# Rev_A.net
KiCad netlist of a schematic drawn in EAGLE
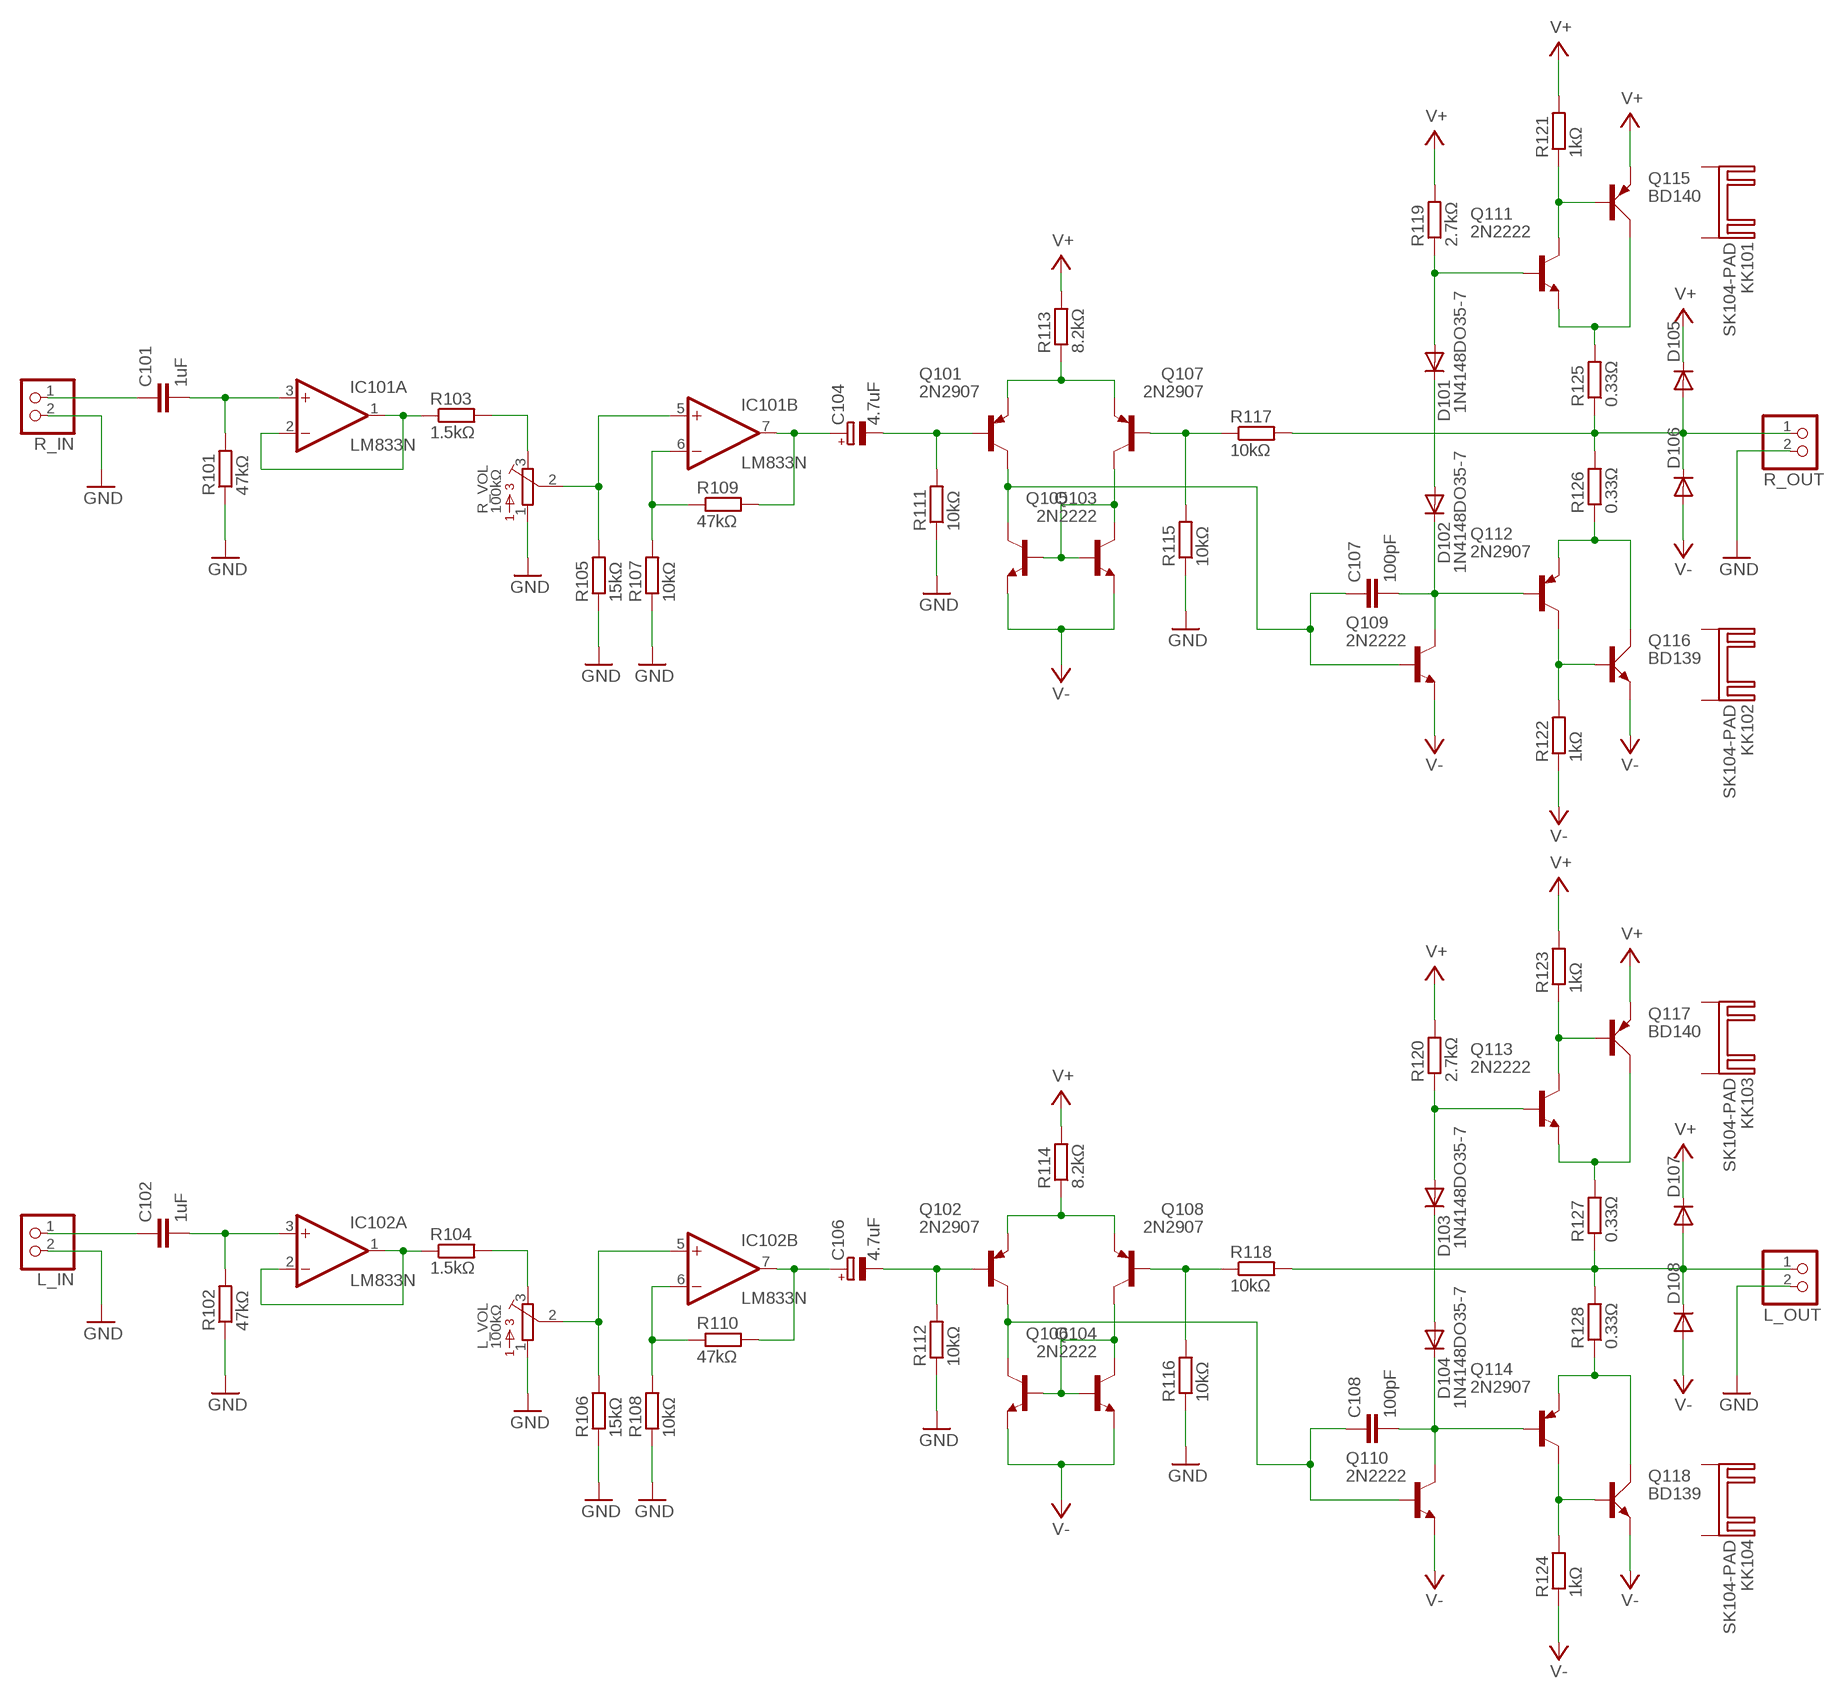
[diagram p0: schematic, sheet 1]
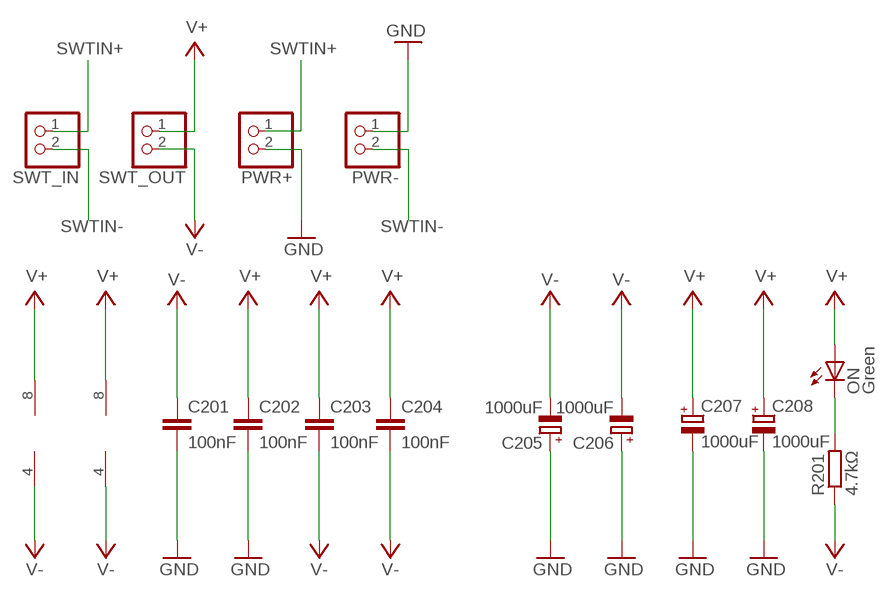
[diagram p1: schematic, sheet 2]

(export (version "E")
  (design (tool "Eeschema 10.0.6"))
  (components
    (comp (ref "C201")
      (value "100nF")
      (footprint "eagle-import:C025-025X050")
      (libsource (lib "eagle-import") (part "C-EU025-025X050"))
    )
    (comp (ref "C202")
      (value "100nF")
      (footprint "eagle-import:C025-025X050")
      (libsource (lib "eagle-import") (part "C-EU025-025X050"))
    )
    (comp (ref "C203")
      (value "100nF")
      (footprint "eagle-import:C025-025X050")
      (libsource (lib "eagle-import") (part "C-EU025-025X050"))
    )
    (comp (ref "C204")
      (value "100nF")
      (footprint "eagle-import:C025-025X050")
      (libsource (lib "eagle-import") (part "C-EU025-025X050"))
    )
    (comp (ref "C205")
      (value "1000uF")
      (footprint "eagle-import:E5-10,5")
      (libsource (lib "eagle-import") (part "CPOL-EUE5-10.5"))
    )
    (comp (ref "C206")
      (value "1000uF")
      (footprint "eagle-import:E5-10,5")
      (libsource (lib "eagle-import") (part "CPOL-EUE5-10.5"))
    )
    (comp (ref "C207")
      (value "1000uF")
      (footprint "eagle-import:E5-10,5")
      (libsource (lib "eagle-import") (part "CPOL-EUE5-10.5"))
    )
    (comp (ref "C208")
      (value "1000uF")
      (footprint "eagle-import:E5-10,5")
      (libsource (lib "eagle-import") (part "CPOL-EUE5-10.5"))
    )
    (comp (ref "IC101")
      (value "LM833N")
      (footprint "eagle-import:DIL08")
      (libsource (lib "eagle-import") (part "LM833N"))
    )
    (comp (ref "IC102")
      (value "LM833N")
      (footprint "eagle-import:DIL08")
      (libsource (lib "eagle-import") (part "LM833N"))
    )
    (comp (ref "ON")
      (value "Green")
      (footprint "eagle-import:LED5MM")
      (libsource (lib "eagle-import") (part "LED5MM"))
    )
    (comp (ref "PWR+")
      (value "JST_2PIN-THM")
      (footprint "eagle-import:JST-PH-2-THM")
      (libsource (lib "eagle-import") (part "JST_2PIN-THM"))
    )
    (comp (ref "PWR-")
      (value "JST_2PIN-THM")
      (footprint "eagle-import:JST-PH-2-THM")
      (libsource (lib "eagle-import") (part "JST_2PIN-THM"))
    )
    (comp (ref "R201")
      (value "4.7kΩ")
      (footprint "eagle-import:0207_10")
      (libsource (lib "eagle-import") (part "R-EU_0207/10"))
    )
    (comp (ref "SWT_IN")
      (value "JST_2PIN-THM")
      (footprint "eagle-import:JST-PH-2-THM")
      (libsource (lib "eagle-import") (part "JST_2PIN-THM"))
    )
    (comp (ref "SWT_OUT")
      (value "JST_2PIN-THM")
      (footprint "eagle-import:JST-PH-2-THM")
      (libsource (lib "eagle-import") (part "JST_2PIN-THM"))
    )
    (comp (ref "C101")
      (value "1uF")
      (footprint "eagle-import:C050-050X075")
      (libsource (lib "eagle-import") (part "C-EU050-050X075"))
    )
    (comp (ref "C102")
      (value "1uF")
      (footprint "eagle-import:C050-050X075")
      (libsource (lib "eagle-import") (part "C-EU050-050X075"))
    )
    (comp (ref "C104")
      (value "4.7uF")
      (footprint "eagle-import:E2-5")
      (libsource (lib "eagle-import") (part "CPOL-EUE2-5"))
    )
    (comp (ref "C106")
      (value "4.7uF")
      (footprint "eagle-import:E2-5")
      (libsource (lib "eagle-import") (part "CPOL-EUE2-5"))
    )
    (comp (ref "C107")
      (value "100pF")
      (footprint "eagle-import:C050-050X075")
      (libsource (lib "eagle-import") (part "C-EU050-050X075"))
    )
    (comp (ref "C108")
      (value "100pF")
      (footprint "eagle-import:C050-050X075")
      (libsource (lib "eagle-import") (part "C-EU050-050X075"))
    )
    (comp (ref "D101")
      (value "1N4148DO35-7")
      (footprint "eagle-import:DO35-7")
      (libsource (lib "eagle-import") (part "1N4148DO35-7"))
    )
    (comp (ref "D102")
      (value "1N4148DO35-7")
      (footprint "eagle-import:DO35-7")
      (libsource (lib "eagle-import") (part "1N4148DO35-7"))
    )
    (comp (ref "D103")
      (value "1N4148DO35-7")
      (footprint "eagle-import:DO35-7")
      (libsource (lib "eagle-import") (part "1N4148DO35-7"))
    )
    (comp (ref "D104")
      (value "1N4148DO35-7")
      (footprint "eagle-import:DO35-7")
      (libsource (lib "eagle-import") (part "1N4148DO35-7"))
    )
    (comp (ref "D105")
      (value "1N4148DO35-7")
      (footprint "eagle-import:DO35-7")
      (libsource (lib "eagle-import") (part "1N4148DO35-7"))
    )
    (comp (ref "D106")
      (value "1N4148DO35-7")
      (footprint "eagle-import:DO35-7")
      (libsource (lib "eagle-import") (part "1N4148DO35-7"))
    )
    (comp (ref "D107")
      (value "1N4148DO35-7")
      (footprint "eagle-import:DO35-7")
      (libsource (lib "eagle-import") (part "1N4148DO35-7"))
    )
    (comp (ref "D108")
      (value "1N4148DO35-7")
      (footprint "eagle-import:DO35-7")
      (libsource (lib "eagle-import") (part "1N4148DO35-7"))
    )
    (comp (ref "KK101")
      (value "SK104-PAD")
      (footprint "eagle-import:SK104-PAD")
      (libsource (lib "eagle-import") (part "SK104-PAD"))
    )
    (comp (ref "KK102")
      (value "SK104-PAD")
      (footprint "eagle-import:SK104-PAD")
      (libsource (lib "eagle-import") (part "SK104-PAD"))
    )
    (comp (ref "KK103")
      (value "SK104-PAD")
      (footprint "eagle-import:SK104-PAD")
      (libsource (lib "eagle-import") (part "SK104-PAD"))
    )
    (comp (ref "KK104")
      (value "SK104-PAD")
      (footprint "eagle-import:SK104-PAD")
      (libsource (lib "eagle-import") (part "SK104-PAD"))
    )
    (comp (ref "L_IN")
      (value "JST_2PIN-THM")
      (footprint "eagle-import:JST-PH-2-THM")
      (libsource (lib "eagle-import") (part "JST_2PIN-THM"))
    )
    (comp (ref "L_OUT")
      (value "JST_2PIN-THM")
      (footprint "eagle-import:JST-PH-2-THM")
      (libsource (lib "eagle-import") (part "JST_2PIN-THM"))
    )
    (comp (ref "L_VOL")
      (value "100kΩ")
      (footprint "eagle-import:3362U")
      (libsource (lib "eagle-import") (part "3362U"))
    )
    (comp (ref "Q101")
      (value "2N2907")
      (footprint "eagle-import:TO18")
      (libsource (lib "eagle-import") (part "2N2907"))
    )
    (comp (ref "Q102")
      (value "2N2907")
      (footprint "eagle-import:TO18")
      (libsource (lib "eagle-import") (part "2N2907"))
    )
    (comp (ref "Q103")
      (value "2N2222")
      (footprint "eagle-import:TO18")
      (libsource (lib "eagle-import") (part "2N2222"))
    )
    (comp (ref "Q104")
      (value "2N2222")
      (footprint "eagle-import:TO18")
      (libsource (lib "eagle-import") (part "2N2222"))
    )
    (comp (ref "Q105")
      (value "2N2222")
      (footprint "eagle-import:TO18")
      (libsource (lib "eagle-import") (part "2N2222"))
    )
    (comp (ref "Q106")
      (value "2N2222")
      (footprint "eagle-import:TO18")
      (libsource (lib "eagle-import") (part "2N2222"))
    )
    (comp (ref "Q107")
      (value "2N2907")
      (footprint "eagle-import:TO18")
      (libsource (lib "eagle-import") (part "2N2907"))
    )
    (comp (ref "Q108")
      (value "2N2907")
      (footprint "eagle-import:TO18")
      (libsource (lib "eagle-import") (part "2N2907"))
    )
    (comp (ref "Q109")
      (value "2N2222")
      (footprint "eagle-import:TO18")
      (libsource (lib "eagle-import") (part "2N2222"))
    )
    (comp (ref "Q110")
      (value "2N2222")
      (footprint "eagle-import:TO18")
      (libsource (lib "eagle-import") (part "2N2222"))
    )
    (comp (ref "Q111")
      (value "2N2222")
      (footprint "eagle-import:TO18")
      (libsource (lib "eagle-import") (part "2N2222"))
    )
    (comp (ref "Q112")
      (value "2N2907")
      (footprint "eagle-import:TO18")
      (libsource (lib "eagle-import") (part "2N2907"))
    )
    (comp (ref "Q113")
      (value "2N2222")
      (footprint "eagle-import:TO18")
      (libsource (lib "eagle-import") (part "2N2222"))
    )
    (comp (ref "Q114")
      (value "2N2907")
      (footprint "eagle-import:TO18")
      (libsource (lib "eagle-import") (part "2N2907"))
    )
    (comp (ref "Q115")
      (value "BD140")
      (footprint "eagle-import:TO126AV")
      (libsource (lib "eagle-import") (part "BD140"))
    )
    (comp (ref "Q116")
      (value "BD139")
      (footprint "eagle-import:TO126AV")
      (libsource (lib "eagle-import") (part "BD139"))
    )
    (comp (ref "Q117")
      (value "BD140")
      (footprint "eagle-import:TO126AV")
      (libsource (lib "eagle-import") (part "BD140"))
    )
    (comp (ref "Q118")
      (value "BD139")
      (footprint "eagle-import:TO126AV")
      (libsource (lib "eagle-import") (part "BD139"))
    )
    (comp (ref "R101")
      (value "47kΩ")
      (footprint "eagle-import:0207_10")
      (libsource (lib "eagle-import") (part "R-EU_0207/10"))
    )
    (comp (ref "R102")
      (value "47kΩ")
      (footprint "eagle-import:0207_10")
      (libsource (lib "eagle-import") (part "R-EU_0207/10"))
    )
    (comp (ref "R103")
      (value "1.5kΩ")
      (footprint "eagle-import:0207_10")
      (libsource (lib "eagle-import") (part "R-EU_0207/10"))
    )
    (comp (ref "R104")
      (value "1.5kΩ")
      (footprint "eagle-import:0207_10")
      (libsource (lib "eagle-import") (part "R-EU_0207/10"))
    )
    (comp (ref "R105")
      (value "15kΩ")
      (footprint "eagle-import:0207_10")
      (libsource (lib "eagle-import") (part "R-EU_0207/10"))
    )
    (comp (ref "R106")
      (value "15kΩ")
      (footprint "eagle-import:0207_10")
      (libsource (lib "eagle-import") (part "R-EU_0207/10"))
    )
    (comp (ref "R107")
      (value "10kΩ")
      (footprint "eagle-import:0207_10")
      (libsource (lib "eagle-import") (part "R-EU_0207/10"))
    )
    (comp (ref "R108")
      (value "10kΩ")
      (footprint "eagle-import:0207_10")
      (libsource (lib "eagle-import") (part "R-EU_0207/10"))
    )
    (comp (ref "R109")
      (value "47kΩ")
      (footprint "eagle-import:0207_10")
      (libsource (lib "eagle-import") (part "R-EU_0207/10"))
    )
    (comp (ref "R110")
      (value "47kΩ")
      (footprint "eagle-import:0207_10")
      (libsource (lib "eagle-import") (part "R-EU_0207/10"))
    )
    (comp (ref "R111")
      (value "10kΩ")
      (footprint "eagle-import:0207_10")
      (libsource (lib "eagle-import") (part "R-EU_0207/10"))
    )
    (comp (ref "R112")
      (value "10kΩ")
      (footprint "eagle-import:0207_10")
      (libsource (lib "eagle-import") (part "R-EU_0207/10"))
    )
    (comp (ref "R113")
      (value "8.2kΩ")
      (footprint "eagle-import:0207_10")
      (libsource (lib "eagle-import") (part "R-EU_0207/10"))
    )
    (comp (ref "R114")
      (value "8.2kΩ")
      (footprint "eagle-import:0207_10")
      (libsource (lib "eagle-import") (part "R-EU_0207/10"))
    )
    (comp (ref "R115")
      (value "10kΩ")
      (footprint "eagle-import:0207_10")
      (libsource (lib "eagle-import") (part "R-EU_0207/10"))
    )
    (comp (ref "R116")
      (value "10kΩ")
      (footprint "eagle-import:0207_10")
      (libsource (lib "eagle-import") (part "R-EU_0207/10"))
    )
    (comp (ref "R117")
      (value "10kΩ")
      (footprint "eagle-import:0207_10")
      (libsource (lib "eagle-import") (part "R-EU_0207/10"))
    )
    (comp (ref "R118")
      (value "10kΩ")
      (footprint "eagle-import:0207_10")
      (libsource (lib "eagle-import") (part "R-EU_0207/10"))
    )
    (comp (ref "R119")
      (value "2.7kΩ")
      (footprint "eagle-import:0207_10")
      (libsource (lib "eagle-import") (part "R-EU_0207/10"))
    )
    (comp (ref "R120")
      (value "2.7kΩ")
      (footprint "eagle-import:0207_10")
      (libsource (lib "eagle-import") (part "R-EU_0207/10"))
    )
    (comp (ref "R121")
      (value "1kΩ")
      (footprint "eagle-import:0207_10")
      (libsource (lib "eagle-import") (part "R-EU_0207/10"))
    )
    (comp (ref "R122")
      (value "1kΩ")
      (footprint "eagle-import:0207_10")
      (libsource (lib "eagle-import") (part "R-EU_0207/10"))
    )
    (comp (ref "R123")
      (value "1kΩ")
      (footprint "eagle-import:0207_10")
      (libsource (lib "eagle-import") (part "R-EU_0207/10"))
    )
    (comp (ref "R124")
      (value "1kΩ")
      (footprint "eagle-import:0207_10")
      (libsource (lib "eagle-import") (part "R-EU_0207/10"))
    )
    (comp (ref "R125")
      (value "0.33Ω")
      (footprint "eagle-import:0309_12")
      (libsource (lib "eagle-import") (part "R-EU_0309/12"))
    )
    (comp (ref "R126")
      (value "0.33Ω")
      (footprint "eagle-import:0309_12")
      (libsource (lib "eagle-import") (part "R-EU_0309/12"))
    )
    (comp (ref "R127")
      (value "0.33Ω")
      (footprint "eagle-import:0309_12")
      (libsource (lib "eagle-import") (part "R-EU_0309/12"))
    )
    (comp (ref "R128")
      (value "0.33Ω")
      (footprint "eagle-import:0309_12")
      (libsource (lib "eagle-import") (part "R-EU_0309/12"))
    )
    (comp (ref "R_IN")
      (value "JST_2PIN-THM")
      (footprint "eagle-import:JST-PH-2-THM")
      (libsource (lib "eagle-import") (part "JST_2PIN-THM"))
    )
    (comp (ref "R_OUT")
      (value "JST_2PIN-THM")
      (footprint "eagle-import:JST-PH-2-THM")
      (libsource (lib "eagle-import") (part "JST_2PIN-THM"))
    )
    (comp (ref "R_VOL")
      (value "100kΩ")
      (footprint "eagle-import:3362U")
      (libsource (lib "eagle-import") (part "3362U"))
    )
  )
  (nets
    (net (code "1") (name "GND") (class "Default")
      (node (ref "C201") (pin "2") (pinfunction "2_2") (pintype "passive"))
      (node (ref "C202") (pin "2") (pinfunction "2_2") (pintype "passive"))
      (node (ref "C205") (pin "+") (pinfunction "+_+") (pintype "passive"))
      (node (ref "C206") (pin "+") (pinfunction "+_+") (pintype "passive"))
      (node (ref "C207") (pin "-") (pinfunction "-_-") (pintype "passive"))
      (node (ref "C208") (pin "-") (pinfunction "-_-") (pintype "passive"))
      (node (ref "L_IN") (pin "2") (pinfunction "1_2") (pintype "passive"))
      (node (ref "L_OUT") (pin "2") (pinfunction "1_2") (pintype "passive"))
      (node (ref "L_VOL") (pin "1") (pinfunction "1_1") (pintype "passive"))
      (node (ref "PWR+") (pin "2") (pinfunction "1_2") (pintype "passive"))
      (node (ref "PWR-") (pin "1") (pinfunction "2_1") (pintype "passive"))
      (node (ref "R101") (pin "1") (pinfunction "1_1") (pintype "passive"))
      (node (ref "R102") (pin "1") (pinfunction "1_1") (pintype "passive"))
      (node (ref "R105") (pin "1") (pinfunction "1_1") (pintype "passive"))
      (node (ref "R106") (pin "1") (pinfunction "1_1") (pintype "passive"))
      (node (ref "R107") (pin "1") (pinfunction "1_1") (pintype "passive"))
      (node (ref "R108") (pin "1") (pinfunction "1_1") (pintype "passive"))
      (node (ref "R111") (pin "1") (pinfunction "1_1") (pintype "passive"))
      (node (ref "R112") (pin "1") (pinfunction "1_1") (pintype "passive"))
      (node (ref "R115") (pin "1") (pinfunction "1_1") (pintype "passive"))
      (node (ref "R116") (pin "1") (pinfunction "1_1") (pintype "passive"))
      (node (ref "R_IN") (pin "2") (pinfunction "1_2") (pintype "passive"))
      (node (ref "R_OUT") (pin "2") (pinfunction "1_2") (pintype "passive"))
      (node (ref "R_VOL") (pin "1") (pinfunction "1_1") (pintype "passive"))
    )
    (net (code "2") (name "Net-(D101-PadC)") (class "Default")
      (node (ref "D101") (pin "C") (pinfunction "C_C") (pintype "passive"))
      (node (ref "D102") (pin "A") (pinfunction "A_A") (pintype "passive"))
    )
    (net (code "3") (name "Net-(D103-PadC)") (class "Default")
      (node (ref "D103") (pin "C") (pinfunction "C_C") (pintype "passive"))
      (node (ref "D104") (pin "A") (pinfunction "A_A") (pintype "passive"))
    )
    (net (code "4") (name "Net-(IC101A-+IN)") (class "Default")
      (node (ref "C101") (pin "2") (pinfunction "2_2") (pintype "passive"))
      (node (ref "IC101") (pin "3") (pinfunction "+IN_3") (pintype "input"))
      (node (ref "R101") (pin "2") (pinfunction "2_2") (pintype "passive"))
    )
    (net (code "5") (name "Net-(IC101A--IN)") (class "Default")
      (node (ref "IC101") (pin "1") (pinfunction "OUT_1") (pintype "output"))
      (node (ref "IC101") (pin "2") (pinfunction "-IN_2") (pintype "input"))
      (node (ref "R103") (pin "1") (pinfunction "1_1") (pintype "passive"))
    )
    (net (code "6") (name "Net-(IC101B-+IN)") (class "Default")
      (node (ref "IC101") (pin "5") (pinfunction "+IN_5") (pintype "input"))
      (node (ref "R105") (pin "2") (pinfunction "2_2") (pintype "passive"))
      (node (ref "R_VOL") (pin "2") (pinfunction "2_2") (pintype "passive"))
    )
    (net (code "7") (name "Net-(IC101B--IN)") (class "Default")
      (node (ref "IC101") (pin "6") (pinfunction "-IN_6") (pintype "input"))
      (node (ref "R107") (pin "2") (pinfunction "2_2") (pintype "passive"))
      (node (ref "R109") (pin "1") (pinfunction "1_1") (pintype "passive"))
    )
    (net (code "8") (name "Net-(IC101B-OUT)") (class "Default")
      (node (ref "C104") (pin "+") (pinfunction "+_+") (pintype "passive"))
      (node (ref "IC101") (pin "7") (pinfunction "OUT_7") (pintype "output"))
      (node (ref "R109") (pin "2") (pinfunction "2_2") (pintype "passive"))
    )
    (net (code "9") (name "Net-(IC102A-+IN)") (class "Default")
      (node (ref "C102") (pin "2") (pinfunction "2_2") (pintype "passive"))
      (node (ref "IC102") (pin "3") (pinfunction "+IN_3") (pintype "input"))
      (node (ref "R102") (pin "2") (pinfunction "2_2") (pintype "passive"))
    )
    (net (code "10") (name "Net-(IC102A--IN)") (class "Default")
      (node (ref "IC102") (pin "1") (pinfunction "OUT_1") (pintype "output"))
      (node (ref "IC102") (pin "2") (pinfunction "-IN_2") (pintype "input"))
      (node (ref "R104") (pin "1") (pinfunction "1_1") (pintype "passive"))
    )
    (net (code "11") (name "Net-(IC102B-+IN)") (class "Default")
      (node (ref "IC102") (pin "5") (pinfunction "+IN_5") (pintype "input"))
      (node (ref "L_VOL") (pin "2") (pinfunction "2_2") (pintype "passive"))
      (node (ref "R106") (pin "2") (pinfunction "2_2") (pintype "passive"))
    )
    (net (code "12") (name "Net-(IC102B--IN)") (class "Default")
      (node (ref "IC102") (pin "6") (pinfunction "-IN_6") (pintype "input"))
      (node (ref "R108") (pin "2") (pinfunction "2_2") (pintype "passive"))
      (node (ref "R110") (pin "1") (pinfunction "1_1") (pintype "passive"))
    )
    (net (code "13") (name "Net-(IC102B-OUT)") (class "Default")
      (node (ref "C106") (pin "+") (pinfunction "+_+") (pintype "passive"))
      (node (ref "IC102") (pin "7") (pinfunction "OUT_7") (pintype "output"))
      (node (ref "R110") (pin "2") (pinfunction "2_2") (pintype "passive"))
    )
    (net (code "14") (name "Net-(L_IN-2)") (class "Default")
      (node (ref "C102") (pin "1") (pinfunction "1_1") (pintype "passive"))
      (node (ref "L_IN") (pin "1") (pinfunction "2_1") (pintype "passive"))
    )
    (net (code "15") (name "Net-(L_OUT-2)") (class "Default")
      (node (ref "D107") (pin "A") (pinfunction "A_A") (pintype "passive"))
      (node (ref "D108") (pin "C") (pinfunction "C_C") (pintype "passive"))
      (node (ref "L_OUT") (pin "1") (pinfunction "2_1") (pintype "passive"))
      (node (ref "R118") (pin "2") (pinfunction "2_2") (pintype "passive"))
      (node (ref "R127") (pin "1") (pinfunction "1_1") (pintype "passive"))
      (node (ref "R128") (pin "2") (pinfunction "2_2") (pintype "passive"))
    )
    (net (code "16") (name "Net-(L_VOL-Pad3)") (class "Default")
      (node (ref "L_VOL") (pin "3") (pinfunction "3_3") (pintype "passive"))
      (node (ref "R104") (pin "2") (pinfunction "2_2") (pintype "passive"))
    )
    (net (code "17") (name "Net-(ON-C)") (class "Default")
      (node (ref "ON") (pin "K") (pinfunction "C_K") (pintype "passive"))
      (node (ref "R201") (pin "2") (pinfunction "2_2") (pintype "passive"))
    )
    (net (code "18") (name "Net-(Q101-B)") (class "Default")
      (node (ref "C104") (pin "-") (pinfunction "-_-") (pintype "passive"))
      (node (ref "Q101") (pin "2") (pinfunction "B_2") (pintype "passive"))
      (node (ref "R111") (pin "2") (pinfunction "2_2") (pintype "passive"))
    )
    (net (code "19") (name "Net-(Q101-C)") (class "Default")
      (node (ref "C107") (pin "1") (pinfunction "1_1") (pintype "passive"))
      (node (ref "Q101") (pin "3") (pinfunction "C_3") (pintype "passive"))
      (node (ref "Q103") (pin "3") (pinfunction "C_3") (pintype "passive"))
      (node (ref "Q109") (pin "2") (pinfunction "B_2") (pintype "passive"))
    )
    (net (code "20") (name "Net-(Q101-E)") (class "Default")
      (node (ref "Q101") (pin "1") (pinfunction "E_1") (pintype "passive"))
      (node (ref "Q107") (pin "1") (pinfunction "E_1") (pintype "passive"))
      (node (ref "R113") (pin "1") (pinfunction "1_1") (pintype "passive"))
    )
    (net (code "21") (name "Net-(Q102-B)") (class "Default")
      (node (ref "C106") (pin "-") (pinfunction "-_-") (pintype "passive"))
      (node (ref "Q102") (pin "2") (pinfunction "B_2") (pintype "passive"))
      (node (ref "R112") (pin "2") (pinfunction "2_2") (pintype "passive"))
    )
    (net (code "22") (name "Net-(Q102-C)") (class "Default")
      (node (ref "C108") (pin "1") (pinfunction "1_1") (pintype "passive"))
      (node (ref "Q102") (pin "3") (pinfunction "C_3") (pintype "passive"))
      (node (ref "Q104") (pin "3") (pinfunction "C_3") (pintype "passive"))
      (node (ref "Q110") (pin "2") (pinfunction "B_2") (pintype "passive"))
    )
    (net (code "23") (name "Net-(Q102-E)") (class "Default")
      (node (ref "Q102") (pin "1") (pinfunction "E_1") (pintype "passive"))
      (node (ref "Q108") (pin "1") (pinfunction "E_1") (pintype "passive"))
      (node (ref "R114") (pin "1") (pinfunction "1_1") (pintype "passive"))
    )
    (net (code "24") (name "Net-(Q103-B)") (class "Default")
      (node (ref "Q103") (pin "2") (pinfunction "B_2") (pintype "passive"))
      (node (ref "Q105") (pin "2") (pinfunction "B_2") (pintype "passive"))
      (node (ref "Q105") (pin "3") (pinfunction "C_3") (pintype "passive"))
      (node (ref "Q107") (pin "3") (pinfunction "C_3") (pintype "passive"))
    )
    (net (code "25") (name "Net-(Q104-B)") (class "Default")
      (node (ref "Q104") (pin "2") (pinfunction "B_2") (pintype "passive"))
      (node (ref "Q106") (pin "2") (pinfunction "B_2") (pintype "passive"))
      (node (ref "Q106") (pin "3") (pinfunction "C_3") (pintype "passive"))
      (node (ref "Q108") (pin "3") (pinfunction "C_3") (pintype "passive"))
    )
    (net (code "26") (name "Net-(Q107-B)") (class "Default")
      (node (ref "Q107") (pin "2") (pinfunction "B_2") (pintype "passive"))
      (node (ref "R115") (pin "2") (pinfunction "2_2") (pintype "passive"))
      (node (ref "R117") (pin "1") (pinfunction "1_1") (pintype "passive"))
    )
    (net (code "27") (name "Net-(Q108-B)") (class "Default")
      (node (ref "Q108") (pin "2") (pinfunction "B_2") (pintype "passive"))
      (node (ref "R116") (pin "2") (pinfunction "2_2") (pintype "passive"))
      (node (ref "R118") (pin "1") (pinfunction "1_1") (pintype "passive"))
    )
    (net (code "28") (name "Net-(Q109-C)") (class "Default")
      (node (ref "C107") (pin "2") (pinfunction "2_2") (pintype "passive"))
      (node (ref "D102") (pin "C") (pinfunction "C_C") (pintype "passive"))
      (node (ref "Q109") (pin "3") (pinfunction "C_3") (pintype "passive"))
      (node (ref "Q112") (pin "2") (pinfunction "B_2") (pintype "passive"))
    )
    (net (code "29") (name "Net-(Q110-C)") (class "Default")
      (node (ref "C108") (pin "2") (pinfunction "2_2") (pintype "passive"))
      (node (ref "D104") (pin "C") (pinfunction "C_C") (pintype "passive"))
      (node (ref "Q110") (pin "3") (pinfunction "C_3") (pintype "passive"))
      (node (ref "Q114") (pin "2") (pinfunction "B_2") (pintype "passive"))
    )
    (net (code "30") (name "Net-(Q111-B)") (class "Default")
      (node (ref "D101") (pin "A") (pinfunction "A_A") (pintype "passive"))
      (node (ref "Q111") (pin "2") (pinfunction "B_2") (pintype "passive"))
      (node (ref "R119") (pin "1") (pinfunction "1_1") (pintype "passive"))
    )
    (net (code "31") (name "Net-(Q111-C)") (class "Default")
      (node (ref "Q111") (pin "3") (pinfunction "C_3") (pintype "passive"))
      (node (ref "Q115") (pin "B") (pinfunction "B_B") (pintype "passive"))
      (node (ref "R121") (pin "1") (pinfunction "1_1") (pintype "passive"))
    )
    (net (code "32") (name "Net-(Q111-E)") (class "Default")
      (node (ref "Q111") (pin "1") (pinfunction "E_1") (pintype "passive"))
      (node (ref "Q115") (pin "C") (pinfunction "C_C") (pintype "passive"))
      (node (ref "R125") (pin "2") (pinfunction "2_2") (pintype "passive"))
    )
    (net (code "33") (name "Net-(Q112-C)") (class "Default")
      (node (ref "Q112") (pin "3") (pinfunction "C_3") (pintype "passive"))
      (node (ref "Q116") (pin "B") (pinfunction "B_B") (pintype "passive"))
      (node (ref "R122") (pin "2") (pinfunction "2_2") (pintype "passive"))
    )
    (net (code "34") (name "Net-(Q112-E)") (class "Default")
      (node (ref "Q112") (pin "1") (pinfunction "E_1") (pintype "passive"))
      (node (ref "Q116") (pin "C") (pinfunction "C_C") (pintype "passive"))
      (node (ref "R126") (pin "1") (pinfunction "1_1") (pintype "passive"))
    )
    (net (code "35") (name "Net-(Q113-B)") (class "Default")
      (node (ref "D103") (pin "A") (pinfunction "A_A") (pintype "passive"))
      (node (ref "Q113") (pin "2") (pinfunction "B_2") (pintype "passive"))
      (node (ref "R120") (pin "1") (pinfunction "1_1") (pintype "passive"))
    )
    (net (code "36") (name "Net-(Q113-C)") (class "Default")
      (node (ref "Q113") (pin "3") (pinfunction "C_3") (pintype "passive"))
      (node (ref "Q117") (pin "B") (pinfunction "B_B") (pintype "passive"))
      (node (ref "R123") (pin "1") (pinfunction "1_1") (pintype "passive"))
    )
    (net (code "37") (name "Net-(Q113-E)") (class "Default")
      (node (ref "Q113") (pin "1") (pinfunction "E_1") (pintype "passive"))
      (node (ref "Q117") (pin "C") (pinfunction "C_C") (pintype "passive"))
      (node (ref "R127") (pin "2") (pinfunction "2_2") (pintype "passive"))
    )
    (net (code "38") (name "Net-(Q114-C)") (class "Default")
      (node (ref "Q114") (pin "3") (pinfunction "C_3") (pintype "passive"))
      (node (ref "Q118") (pin "B") (pinfunction "B_B") (pintype "passive"))
      (node (ref "R124") (pin "2") (pinfunction "2_2") (pintype "passive"))
    )
    (net (code "39") (name "Net-(Q114-E)") (class "Default")
      (node (ref "Q114") (pin "1") (pinfunction "E_1") (pintype "passive"))
      (node (ref "Q118") (pin "C") (pinfunction "C_C") (pintype "passive"))
      (node (ref "R128") (pin "1") (pinfunction "1_1") (pintype "passive"))
    )
    (net (code "40") (name "Net-(R103-Pad2)") (class "Default")
      (node (ref "R103") (pin "2") (pinfunction "2_2") (pintype "passive"))
      (node (ref "R_VOL") (pin "3") (pinfunction "3_3") (pintype "passive"))
    )
    (net (code "41") (name "Net-(R_IN-2)") (class "Default")
      (node (ref "C101") (pin "1") (pinfunction "1_1") (pintype "passive"))
      (node (ref "R_IN") (pin "1") (pinfunction "2_1") (pintype "passive"))
    )
    (net (code "42") (name "Net-(R_OUT-2)") (class "Default")
      (node (ref "D105") (pin "A") (pinfunction "A_A") (pintype "passive"))
      (node (ref "D106") (pin "C") (pinfunction "C_C") (pintype "passive"))
      (node (ref "R117") (pin "2") (pinfunction "2_2") (pintype "passive"))
      (node (ref "R125") (pin "1") (pinfunction "1_1") (pintype "passive"))
      (node (ref "R126") (pin "2") (pinfunction "2_2") (pintype "passive"))
      (node (ref "R_OUT") (pin "1") (pinfunction "2_1") (pintype "passive"))
    )
    (net (code "43") (name "SWTIN+") (class "Default")
      (node (ref "PWR+") (pin "1") (pinfunction "2_1") (pintype "passive"))
      (node (ref "SWT_IN") (pin "1") (pinfunction "2_1") (pintype "passive"))
    )
    (net (code "44") (name "SWTIN-") (class "Default")
      (node (ref "PWR-") (pin "2") (pinfunction "1_2") (pintype "passive"))
      (node (ref "SWT_IN") (pin "2") (pinfunction "1_2") (pintype "passive"))
    )
    (net (code "45") (name "V+") (class "Default")
      (node (ref "C202") (pin "1") (pinfunction "1_1") (pintype "passive"))
      (node (ref "C203") (pin "1") (pinfunction "1_1") (pintype "passive"))
      (node (ref "C204") (pin "1") (pinfunction "1_1") (pintype "passive"))
      (node (ref "C207") (pin "+") (pinfunction "+_+") (pintype "passive"))
      (node (ref "C208") (pin "+") (pinfunction "+_+") (pintype "passive"))
      (node (ref "D105") (pin "C") (pinfunction "C_C") (pintype "passive"))
      (node (ref "D107") (pin "C") (pinfunction "C_C") (pintype "passive"))
      (node (ref "IC101") (pin "8") (pinfunction "V+_8") (pintype "power_in"))
      (node (ref "IC102") (pin "8") (pinfunction "V+_8") (pintype "power_in"))
      (node (ref "ON") (pin "A") (pinfunction "A_A") (pintype "passive"))
      (node (ref "Q115") (pin "E") (pinfunction "E_E") (pintype "passive"))
      (node (ref "Q117") (pin "E") (pinfunction "E_E") (pintype "passive"))
      (node (ref "R113") (pin "2") (pinfunction "2_2") (pintype "passive"))
      (node (ref "R114") (pin "2") (pinfunction "2_2") (pintype "passive"))
      (node (ref "R119") (pin "2") (pinfunction "2_2") (pintype "passive"))
      (node (ref "R120") (pin "2") (pinfunction "2_2") (pintype "passive"))
      (node (ref "R121") (pin "2") (pinfunction "2_2") (pintype "passive"))
      (node (ref "R123") (pin "2") (pinfunction "2_2") (pintype "passive"))
      (node (ref "SWT_OUT") (pin "1") (pinfunction "2_1") (pintype "passive"))
    )
    (net (code "46") (name "V-") (class "Default")
      (node (ref "C201") (pin "1") (pinfunction "1_1") (pintype "passive"))
      (node (ref "C203") (pin "2") (pinfunction "2_2") (pintype "passive"))
      (node (ref "C204") (pin "2") (pinfunction "2_2") (pintype "passive"))
      (node (ref "C205") (pin "-") (pinfunction "-_-") (pintype "passive"))
      (node (ref "C206") (pin "-") (pinfunction "-_-") (pintype "passive"))
      (node (ref "D106") (pin "A") (pinfunction "A_A") (pintype "passive"))
      (node (ref "D108") (pin "A") (pinfunction "A_A") (pintype "passive"))
      (node (ref "IC101") (pin "4") (pinfunction "V-_4") (pintype "power_in"))
      (node (ref "IC102") (pin "4") (pinfunction "V-_4") (pintype "power_in"))
      (node (ref "Q103") (pin "1") (pinfunction "E_1") (pintype "passive"))
      (node (ref "Q104") (pin "1") (pinfunction "E_1") (pintype "passive"))
      (node (ref "Q105") (pin "1") (pinfunction "E_1") (pintype "passive"))
      (node (ref "Q106") (pin "1") (pinfunction "E_1") (pintype "passive"))
      (node (ref "Q109") (pin "1") (pinfunction "E_1") (pintype "passive"))
      (node (ref "Q110") (pin "1") (pinfunction "E_1") (pintype "passive"))
      (node (ref "Q116") (pin "E") (pinfunction "E_E") (pintype "passive"))
      (node (ref "Q118") (pin "E") (pinfunction "E_E") (pintype "passive"))
      (node (ref "R122") (pin "1") (pinfunction "1_1") (pintype "passive"))
      (node (ref "R124") (pin "1") (pinfunction "1_1") (pintype "passive"))
      (node (ref "R201") (pin "1") (pinfunction "1_1") (pintype "passive"))
      (node (ref "SWT_OUT") (pin "2") (pinfunction "1_2") (pintype "passive"))
    )
    (net (code "47") (name "unconnected-(KK101-K-PadK1)") (class "Default")
      (node (ref "KK101") (pin "K1") (pinfunction "K_K1") (pintype "passive"))
    )
    (net (code "48") (name "unconnected-(KK101-K-PadK2)") (class "Default")
      (node (ref "KK101") (pin "K2") (pinfunction "K_K2") (pintype "passive"))
    )
    (net (code "49") (name "unconnected-(KK102-K-PadK1)") (class "Default")
      (node (ref "KK102") (pin "K1") (pinfunction "K_K1") (pintype "passive"))
    )
    (net (code "50") (name "unconnected-(KK102-K-PadK2)") (class "Default")
      (node (ref "KK102") (pin "K2") (pinfunction "K_K2") (pintype "passive"))
    )
    (net (code "51") (name "unconnected-(KK103-K-PadK1)") (class "Default")
      (node (ref "KK103") (pin "K1") (pinfunction "K_K1") (pintype "passive"))
    )
    (net (code "52") (name "unconnected-(KK103-K-PadK2)") (class "Default")
      (node (ref "KK103") (pin "K2") (pinfunction "K_K2") (pintype "passive"))
    )
    (net (code "53") (name "unconnected-(KK104-K-PadK1)") (class "Default")
      (node (ref "KK104") (pin "K1") (pinfunction "K_K1") (pintype "passive"))
    )
    (net (code "54") (name "unconnected-(KK104-K-PadK2)") (class "Default")
      (node (ref "KK104") (pin "K2") (pinfunction "K_K2") (pintype "passive"))
    )
  )
)
